# AS5040_Motor.net
KiCad netlist of a schematic drawn in EAGLE
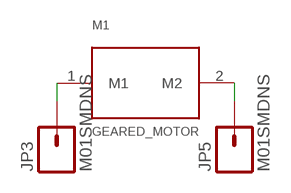
[diagram p0: schematic, sheet 1]

(export (version "E")
  (design (tool "Eeschema 10.0.6"))
  (components
    (comp (ref "JP3")
      (value "M01SMDNS")
      (footprint "eagle-import:1X01NS")
      (libsource (lib "eagle-import") (part "M01SMDNS"))
    )
    (comp (ref "JP5")
      (value "M01SMDNS")
      (footprint "eagle-import:1X01NS")
      (libsource (lib "eagle-import") (part "M01SMDNS"))
    )
    (comp (ref "M1")
      (value "GEARED_MOTOR")
      (footprint "eagle-import:GEARED_MOTOR")
      (libsource (lib "eagle-import") (part "GEARED_MOTOR"))
    )
  )
  (nets
    (net (code "1") (name "Net-(M1-M1)") (class "Default")
      (node (ref "JP3") (pin "1") (pinfunction "1_1") (pintype "passive"))
      (node (ref "M1") (pin "1") (pinfunction "M1_1") (pintype "bidirectional"))
    )
    (net (code "2") (name "Net-(M1-M2)") (class "Default")
      (node (ref "JP5") (pin "1") (pinfunction "1_1") (pintype "passive"))
      (node (ref "M1") (pin "2") (pinfunction "M2_2") (pintype "bidirectional"))
    )
  )
)
